# SCH_POWER.net
KiCad netlist of a schematic drawn in Altium Designer
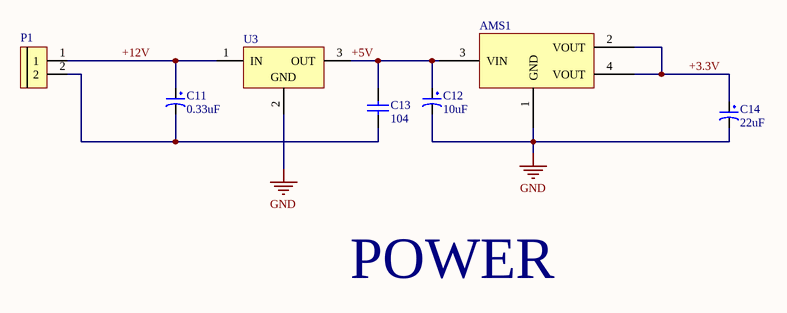
[diagram p0: SCH_POWER.SchDoc]

(export (version "E")
  (design (tool "Eeschema 10.0.6"))
  (components
    (comp (ref "AMS1")
      (value "~")
      (footprint "SOT223")
      (description "Dán")
      (libsource (lib "Altium_Lib_by_KhueNguyenCreator") (part "AMS1117 SMD"))
    )
    (comp (ref "C11")
      (value "0.33uF")
      (footprint "tu hoa 5mm")
      (description "Cắm")
      (libsource (lib "Altium_Lib_by_KhueNguyenCreator") (part "Tu Hoa 0.33uF 50V 5x11"))
    )
    (comp (ref "C12")
      (value "10uF")
      (footprint "tu hoa 13mm")
      (description "Cắm")
      (libsource (lib "Altium_Lib_by_KhueNguyenCreator") (part "Tu Hoa 10uF 450V 13x20"))
    )
    (comp (ref "C13")
      (value "104")
      (footprint "tu 1206")
      (description "Dán")
      (libsource (lib "Altium_Lib_by_KhueNguyenCreator") (part "Tu 1206 104 50V 20%"))
    )
    (comp (ref "C14")
      (value "22uF")
      (footprint "tu hoa 4mm")
      (description "Cắm")
      (libsource (lib "Altium_Lib_by_KhueNguyenCreator") (part "Tu Hoa 22uF 16V 4x7"))
    )
    (comp (ref "P1")
      (value "~")
      (footprint "CON 2 2EDG5.08")
      (description "Cắm")
      (libsource (lib "Altium_Lib_by_KhueNguyenCreator") (part "CON 2 EDG5.08"))
    )
    (comp (ref "U3")
      (value "~")
      (footprint "TO252")
      (description "Dán")
      (libsource (lib "Altium_Lib_by_KhueNguyenCreator") (part "78M05 SMD TO252"))
    )
  )
  (nets
    (net (code "1") (name "/+3.3V") (class "Default")
      (node (ref "AMS1") (pin "2") (pinfunction "VOUT_2") (pintype "passive"))
      (node (ref "AMS1") (pin "4") (pinfunction "VOUT_4") (pintype "passive"))
      (node (ref "C14") (pin "1") (pinfunction "1_1") (pintype "passive"))
    )
    (net (code "2") (name "/+5V") (class "Default")
      (node (ref "AMS1") (pin "3") (pinfunction "VIN_3") (pintype "passive"))
      (node (ref "C12") (pin "1") (pinfunction "1_1") (pintype "passive"))
      (node (ref "C13") (pin "1") (pinfunction "1_1") (pintype "passive"))
      (node (ref "U3") (pin "3") (pinfunction "OUT_3") (pintype "power_in"))
    )
    (net (code "3") (name "/+12V") (class "Default")
      (node (ref "C11") (pin "1") (pinfunction "1_1") (pintype "passive"))
      (node (ref "P1") (pin "1") (pinfunction "1_1") (pintype "passive"))
      (node (ref "U3") (pin "1") (pinfunction "IN_1") (pintype "power_in"))
    )
    (net (code "4") (name "GND") (class "Default")
      (node (ref "AMS1") (pin "1") (pinfunction "GND_1") (pintype "passive"))
      (node (ref "C12") (pin "2") (pinfunction "2_2") (pintype "passive"))
      (node (ref "C14") (pin "2") (pinfunction "2_2") (pintype "passive"))
      (node (ref "U3") (pin "2") (pinfunction "GND_2") (pintype "power_in"))
    )
    (net (code "5") (name "Net-(C11-Pad2)") (class "Default")
      (node (ref "C11") (pin "2") (pinfunction "2_2") (pintype "passive"))
      (node (ref "C13") (pin "2") (pinfunction "2_2") (pintype "passive"))
      (node (ref "P1") (pin "2") (pinfunction "2_2") (pintype "passive"))
    )
  )
)
